# LIN-BUS.net
KiCad netlist of a schematic drawn in Altium Designer
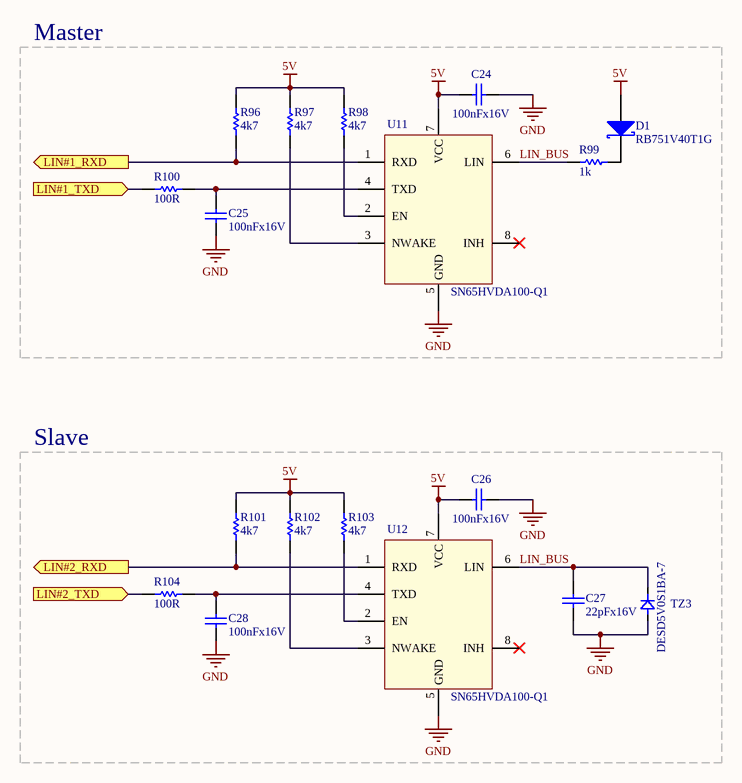
[diagram p0: LIN-BUS.SchDoc]

(export (version "E")
  (design (tool "Eeschema 10.0.6"))
  (components
    (comp (ref "C24")
      (value "100nFx16V")
      (footprint "DISC-0603")
      (description "Capacitor")
      (libsource (lib "IntLib") (part "Cap"))
    )
    (comp (ref "C25")
      (value "100nFx16V")
      (footprint "DISC-0603")
      (description "Capacitor")
      (libsource (lib "IntLib") (part "Cap"))
    )
    (comp (ref "C26")
      (value "100nFx16V")
      (footprint "DISC-0603")
      (description "Capacitor")
      (libsource (lib "IntLib") (part "Cap"))
    )
    (comp (ref "C27") (value "22pFx16V") (footprint "DISC-0603") (libsource (lib "IntLib") (part "Cap")))
    (comp (ref "C28")
      (value "100nFx16V")
      (footprint "DISC-0603")
      (description "Capacitor")
      (libsource (lib "IntLib") (part "Cap"))
    )
    (comp (ref "D1")
      (value "RB751V40T1G")
      (footprint "DISC-SOD-323")
      (description "Schottky Diode")
      (libsource (lib "IntLib") (part "D Schottky"))
    )
    (comp (ref "R96")
      (value "4k7")
      (footprint "DISC-0603")
      (description "Resistor")
      (libsource (lib "IntLib") (part "Res"))
    )
    (comp (ref "R97")
      (value "4k7")
      (footprint "DISC-0603")
      (description "Resistor")
      (libsource (lib "IntLib") (part "Res"))
    )
    (comp (ref "R98")
      (value "4k7")
      (footprint "DISC-0603")
      (description "Resistor")
      (libsource (lib "IntLib") (part "Res"))
    )
    (comp (ref "R99")
      (value "1k")
      (footprint "DISC-0603")
      (description "Resistor")
      (libsource (lib "IntLib") (part "Res"))
    )
    (comp (ref "R100")
      (value "100R")
      (footprint "DISC-0603")
      (description "Resistor")
      (libsource (lib "IntLib") (part "Res"))
    )
    (comp (ref "R101")
      (value "4k7")
      (footprint "DISC-0603")
      (description "Resistor")
      (libsource (lib "IntLib") (part "Res"))
    )
    (comp (ref "R102")
      (value "4k7")
      (footprint "DISC-0603")
      (description "Resistor")
      (libsource (lib "IntLib") (part "Res"))
    )
    (comp (ref "R103")
      (value "4k7")
      (footprint "DISC-0603")
      (description "Resistor")
      (libsource (lib "IntLib") (part "Res"))
    )
    (comp (ref "R104")
      (value "100R")
      (footprint "DISC-0603")
      (description "Resistor")
      (libsource (lib "IntLib") (part "Res"))
    )
    (comp (ref "TZ3")
      (value "DESD5V0S1BA-7")
      (footprint "DISC-SOD-323")
      (description "TVZ-Unidirectional")
      (libsource (lib "IntLib") (part "TVZ-Unidirectional"))
    )
    (comp (ref "U11")
      (value "SN65HVDA100-Q1")
      (footprint "CI-SOIC-8")
      (description "LIN Transceiver")
      (libsource (lib "IntLib") (part "SN65HVDA100-Q1"))
    )
    (comp (ref "U12")
      (value "SN65HVDA100-Q1")
      (footprint "CI-SOIC-8")
      (description "LIN Transceiver")
      (libsource (lib "IntLib") (part "SN65HVDA100-Q1"))
    )
  )
  (nets
    (net (code "1") (name "/LIN#1_RXD") (class "Default")
      (node (ref "R96") (pin "1") (pinfunction "1_1") (pintype "passive"))
      (node (ref "U11") (pin "1") (pinfunction "RXD_1") (pintype "passive"))
    )
    (net (code "2") (name "/LIN#1_TXD") (class "Default")
      (node (ref "R100") (pin "2") (pinfunction "2_2") (pintype "passive"))
    )
    (net (code "3") (name "/LIN#2_RXD") (class "Default")
      (node (ref "R101") (pin "1") (pinfunction "1_1") (pintype "passive"))
      (node (ref "U12") (pin "1") (pinfunction "RXD_1") (pintype "passive"))
    )
    (net (code "4") (name "/LIN#2_TXD") (class "Default")
      (node (ref "R104") (pin "2") (pinfunction "2_2") (pintype "passive"))
    )
    (net (code "5") (name "/LIN_BUS") (class "Default")
      (node (ref "C27") (pin "2") (pinfunction "2_2") (pintype "passive"))
      (node (ref "R99") (pin "2") (pinfunction "2_2") (pintype "passive"))
      (node (ref "TZ3") (pin "2") (pinfunction "C_2") (pintype "passive"))
      (node (ref "U11") (pin "6") (pinfunction "LIN_6") (pintype "passive"))
      (node (ref "U12") (pin "6") (pinfunction "LIN_6") (pintype "passive"))
    )
    (net (code "6") (name "5V") (class "Default")
      (node (ref "C24") (pin "2") (pinfunction "2_2") (pintype "passive"))
      (node (ref "C26") (pin "2") (pinfunction "2_2") (pintype "passive"))
      (node (ref "D1") (pin "1") (pinfunction "A_1") (pintype "passive"))
      (node (ref "R101") (pin "2") (pinfunction "2_2") (pintype "passive"))
      (node (ref "R102") (pin "2") (pinfunction "2_2") (pintype "passive"))
      (node (ref "R103") (pin "2") (pinfunction "2_2") (pintype "passive"))
      (node (ref "R96") (pin "2") (pinfunction "2_2") (pintype "passive"))
      (node (ref "R97") (pin "2") (pinfunction "2_2") (pintype "passive"))
      (node (ref "R98") (pin "2") (pinfunction "2_2") (pintype "passive"))
      (node (ref "U11") (pin "7") (pinfunction "VCC_7") (pintype "power_in"))
      (node (ref "U12") (pin "7") (pinfunction "VCC_7") (pintype "power_in"))
    )
    (net (code "7") (name "GND") (class "Default")
      (node (ref "C24") (pin "1") (pinfunction "1_1") (pintype "passive"))
      (node (ref "C25") (pin "1") (pinfunction "1_1") (pintype "passive"))
      (node (ref "C26") (pin "1") (pinfunction "1_1") (pintype "passive"))
      (node (ref "C27") (pin "1") (pinfunction "1_1") (pintype "passive"))
      (node (ref "C28") (pin "1") (pinfunction "1_1") (pintype "passive"))
      (node (ref "TZ3") (pin "1") (pinfunction "A_1") (pintype "passive"))
      (node (ref "U11") (pin "5") (pinfunction "GND_5") (pintype "power_in"))
      (node (ref "U12") (pin "5") (pinfunction "GND_5") (pintype "power_in"))
    )
    (net (code "8") (name "Net-(D1-K)") (class "Default")
      (node (ref "D1") (pin "2") (pinfunction "K_2") (pintype "passive"))
      (node (ref "R99") (pin "1") (pinfunction "1_1") (pintype "passive"))
    )
    (net (code "9") (name "Net-(U11-EN)") (class "Default")
      (node (ref "R98") (pin "1") (pinfunction "1_1") (pintype "passive"))
      (node (ref "U11") (pin "2") (pinfunction "EN_2") (pintype "passive"))
    )
    (net (code "10") (name "Net-(U11-NWAKE)") (class "Default")
      (node (ref "R97") (pin "1") (pinfunction "1_1") (pintype "passive"))
      (node (ref "U11") (pin "3") (pinfunction "NWAKE_3") (pintype "passive"))
    )
    (net (code "11") (name "Net-(U11-TXD)") (class "Default")
      (node (ref "C25") (pin "2") (pinfunction "2_2") (pintype "passive"))
      (node (ref "R100") (pin "1") (pinfunction "1_1") (pintype "passive"))
      (node (ref "U11") (pin "4") (pinfunction "TXD_4") (pintype "passive"))
    )
    (net (code "12") (name "Net-(U12-EN)") (class "Default")
      (node (ref "R103") (pin "1") (pinfunction "1_1") (pintype "passive"))
      (node (ref "U12") (pin "2") (pinfunction "EN_2") (pintype "passive"))
    )
    (net (code "13") (name "Net-(U12-NWAKE)") (class "Default")
      (node (ref "R102") (pin "1") (pinfunction "1_1") (pintype "passive"))
      (node (ref "U12") (pin "3") (pinfunction "NWAKE_3") (pintype "passive"))
    )
    (net (code "14") (name "Net-(U12-TXD)") (class "Default")
      (node (ref "C28") (pin "2") (pinfunction "2_2") (pintype "passive"))
      (node (ref "R104") (pin "1") (pinfunction "1_1") (pintype "passive"))
      (node (ref "U12") (pin "4") (pinfunction "TXD_4") (pintype "passive"))
    )
    (net (code "15") (name "unconnected-(U11-INH-Pad8)") (class "Default")
      (node (ref "U11") (pin "8") (pinfunction "INH_8") (pintype "passive+no_connect"))
    )
    (net (code "16") (name "unconnected-(U12-INH-Pad8)") (class "Default")
      (node (ref "U12") (pin "8") (pinfunction "INH_8") (pintype "passive+no_connect"))
    )
  )
)
